# ServoDriver.net
KiCad netlist of a schematic drawn in Altium Designer
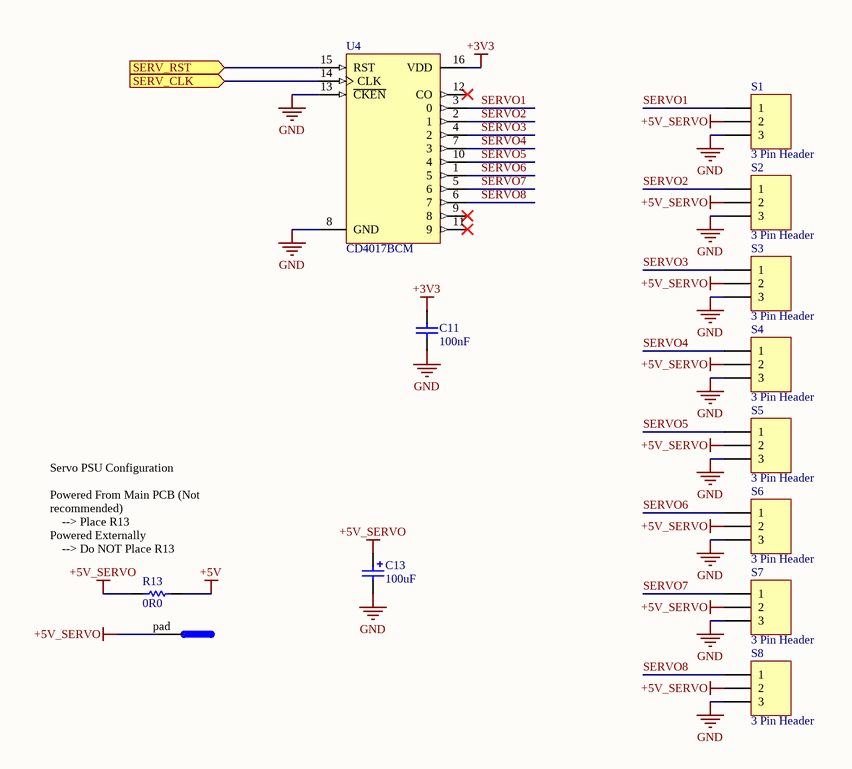
[diagram p0: ServoDriver.SchDoc]

(export (version "E")
  (design (tool "Eeschema 10.0.6"))
  (components
    (comp (ref "C11")
      (value "100nF")
      (footprint "GRC PCB library:0603")
      (description "CAP CER .10UF 50V X5R 0603")
      (fields (field (name "MANUFACTURER") "Taiyo Yuden"))
      (libsource (lib "GRC sch library") (part "CP_100nF 0603"))
    )
    (comp (ref "C13")
      (value "100uF")
      (footprint "CAP_ELECTRO_6.3x11")
      (description "Polarized Capacitor (Radial)")
      (fields (field (name "MANUFACTURER") "Multicomp") (field (name "Comment") "CP_POL_100uF_25V_6.3mm"))
      (libsource (lib "GRC sch library") (part "CP_POL_100uF_25V_6.3mm"))
    )
    (comp (ref "PS")
      (value "~")
      (footprint "PAD_ROUND")
      (description "Pad")
      (libsource (lib "GRC sch library") (part "JP_pad"))
    )
    (comp (ref "R13")
      (value "0R0")
      (footprint "0805")
      (description "RES 0.0 OHM 1/10W 5% 1206 SMD")
      (fields (field (name "MANUFACTURER") "Rohm"))
      (libsource (lib "GRC sch library") (part "RS_0R0 0603"))
    )
    (comp (ref "S1")
      (value "3 Pin Header")
      (footprint "G_HDR1X3_RND_PIN1_NO_OVERLAY")
      (description "CONN HDR VERT 3POS .100\" SNGL")
      (libsource (lib "GRC sch library") (part "JP_3PIN HDR"))
    )
    (comp (ref "S2")
      (value "3 Pin Header")
      (footprint "G_HDR1X3_RND_PIN1_NO_OVERLAY")
      (description "CONN HDR VERT 3POS .100\" SNGL")
      (libsource (lib "GRC sch library") (part "JP_3PIN HDR"))
    )
    (comp (ref "S3")
      (value "3 Pin Header")
      (footprint "G_HDR1X3_RND_PIN1_NO_OVERLAY")
      (description "CONN HDR VERT 3POS .100\" SNGL")
      (libsource (lib "GRC sch library") (part "JP_3PIN HDR"))
    )
    (comp (ref "S4")
      (value "3 Pin Header")
      (footprint "G_HDR1X3_RND_PIN1_NO_OVERLAY")
      (description "CONN HDR VERT 3POS .100\" SNGL")
      (libsource (lib "GRC sch library") (part "JP_3PIN HDR"))
    )
    (comp (ref "S5")
      (value "3 Pin Header")
      (footprint "G_HDR1X3_RND_PIN1_NO_OVERLAY")
      (description "CONN HDR VERT 3POS .100\" SNGL")
      (libsource (lib "GRC sch library") (part "JP_3PIN HDR"))
    )
    (comp (ref "S6")
      (value "3 Pin Header")
      (footprint "G_HDR1X3_RND_PIN1_NO_OVERLAY")
      (description "CONN HDR VERT 3POS .100\" SNGL")
      (libsource (lib "GRC sch library") (part "JP_3PIN HDR"))
    )
    (comp (ref "S7")
      (value "3 Pin Header")
      (footprint "G_HDR1X3_RND_PIN1_NO_OVERLAY")
      (description "CONN HDR VERT 3POS .100\" SNGL")
      (libsource (lib "GRC sch library") (part "JP_3PIN HDR"))
    )
    (comp (ref "S8")
      (value "3 Pin Header")
      (footprint "G_HDR1X3_RND_PIN1_NO_OVERLAY")
      (description "CONN HDR VERT 3POS .100\" SNGL")
      (libsource (lib "GRC sch library") (part "JP_3PIN HDR"))
    )
    (comp (ref "U4")
      (value "CD4017BCM")
      (footprint "PW016")
      (description "Decade Counter/Divider with 10 Decoded Outputs")
      (fields (field (name "PUBLISHER") "Altium Limited"))
      (libsource (lib "FSC Logic Counter") (part "CD4017BCM"))
    )
  )
  (nets
    (net (code "1") (name "+3V3") (class "Default")
      (node (ref "C11") (pin "2") (pinfunction "2_2") (pintype "passive"))
      (node (ref "U4") (pin "16") (pinfunction "VDD_16") (pintype "power_in"))
    )
    (net (code "2") (name "+5V") (class "Default")
      (node (ref "R13") (pin "1") (pinfunction "1_1") (pintype "passive"))
    )
    (net (code "3") (name "+5V_SERVO") (class "Default")
      (node (ref "C13") (pin "1") (pinfunction "1_1") (pintype "passive"))
      (node (ref "PS") (pin "pad") (pintype "passive"))
      (node (ref "R13") (pin "2") (pinfunction "2_2") (pintype "passive"))
      (node (ref "S1") (pin "2") (pinfunction "2_2") (pintype "passive"))
      (node (ref "S2") (pin "2") (pinfunction "2_2") (pintype "passive"))
      (node (ref "S3") (pin "2") (pinfunction "2_2") (pintype "passive"))
      (node (ref "S4") (pin "2") (pinfunction "2_2") (pintype "passive"))
      (node (ref "S5") (pin "2") (pinfunction "2_2") (pintype "passive"))
      (node (ref "S6") (pin "2") (pinfunction "2_2") (pintype "passive"))
      (node (ref "S7") (pin "2") (pinfunction "2_2") (pintype "passive"))
      (node (ref "S8") (pin "2") (pinfunction "2_2") (pintype "passive"))
    )
    (net (code "4") (name "/SERVO1") (class "Default")
      (node (ref "S1") (pin "1") (pinfunction "1_1") (pintype "passive"))
      (node (ref "U4") (pin "3") (pinfunction "0_3") (pintype "output"))
    )
    (net (code "5") (name "/SERVO2") (class "Default")
      (node (ref "S2") (pin "1") (pinfunction "1_1") (pintype "passive"))
      (node (ref "U4") (pin "2") (pinfunction "1_2") (pintype "output"))
    )
    (net (code "6") (name "/SERVO3") (class "Default")
      (node (ref "S3") (pin "1") (pinfunction "1_1") (pintype "passive"))
      (node (ref "U4") (pin "4") (pinfunction "2_4") (pintype "output"))
    )
    (net (code "7") (name "/SERVO4") (class "Default")
      (node (ref "S4") (pin "1") (pinfunction "1_1") (pintype "passive"))
      (node (ref "U4") (pin "7") (pinfunction "3_7") (pintype "output"))
    )
    (net (code "8") (name "/SERVO5") (class "Default")
      (node (ref "S5") (pin "1") (pinfunction "1_1") (pintype "passive"))
      (node (ref "U4") (pin "10") (pinfunction "4_10") (pintype "output"))
    )
    (net (code "9") (name "/SERVO6") (class "Default")
      (node (ref "S6") (pin "1") (pinfunction "1_1") (pintype "passive"))
      (node (ref "U4") (pin "1") (pinfunction "5_1") (pintype "output"))
    )
    (net (code "10") (name "/SERVO7") (class "Default")
      (node (ref "S7") (pin "1") (pinfunction "1_1") (pintype "passive"))
      (node (ref "U4") (pin "5") (pinfunction "6_5") (pintype "output"))
    )
    (net (code "11") (name "/SERVO8") (class "Default")
      (node (ref "S8") (pin "1") (pinfunction "1_1") (pintype "passive"))
      (node (ref "U4") (pin "6") (pinfunction "7_6") (pintype "output"))
    )
    (net (code "12") (name "/SERV_CLK") (class "Default")
      (node (ref "U4") (pin "14") (pinfunction "CLK_14") (pintype "input"))
    )
    (net (code "13") (name "/SERV_RST") (class "Default")
      (node (ref "U4") (pin "15") (pinfunction "RST_15") (pintype "input"))
    )
    (net (code "14") (name "GND") (class "Default")
      (node (ref "C11") (pin "1") (pinfunction "1_1") (pintype "passive"))
      (node (ref "C13") (pin "2") (pinfunction "2_2") (pintype "passive"))
      (node (ref "S1") (pin "3") (pinfunction "3_3") (pintype "passive"))
      (node (ref "S2") (pin "3") (pinfunction "3_3") (pintype "passive"))
      (node (ref "S3") (pin "3") (pinfunction "3_3") (pintype "passive"))
      (node (ref "S4") (pin "3") (pinfunction "3_3") (pintype "passive"))
      (node (ref "S5") (pin "3") (pinfunction "3_3") (pintype "passive"))
      (node (ref "S6") (pin "3") (pinfunction "3_3") (pintype "passive"))
      (node (ref "S7") (pin "3") (pinfunction "3_3") (pintype "passive"))
      (node (ref "S8") (pin "3") (pinfunction "3_3") (pintype "passive"))
      (node (ref "U4") (pin "13") (pinfunction "~{CKEN}_13") (pintype "input"))
      (node (ref "U4") (pin "8") (pinfunction "GND_8") (pintype "power_in"))
    )
    (net (code "15") (name "unconnected-(U4-8-Pad9)") (class "Default")
      (node (ref "U4") (pin "9") (pinfunction "8_9") (pintype "output+no_connect"))
    )
    (net (code "16") (name "unconnected-(U4-9-Pad11)") (class "Default")
      (node (ref "U4") (pin "11") (pinfunction "9_11") (pintype "output+no_connect"))
    )
    (net (code "17") (name "unconnected-(U4-CO-Pad12)") (class "Default")
      (node (ref "U4") (pin "12") (pinfunction "CO_12") (pintype "output+no_connect"))
    )
  )
)
